# OctoSlime_Switch_Unit.net
KiCad netlist of a schematic drawn in EasyEDA Pro
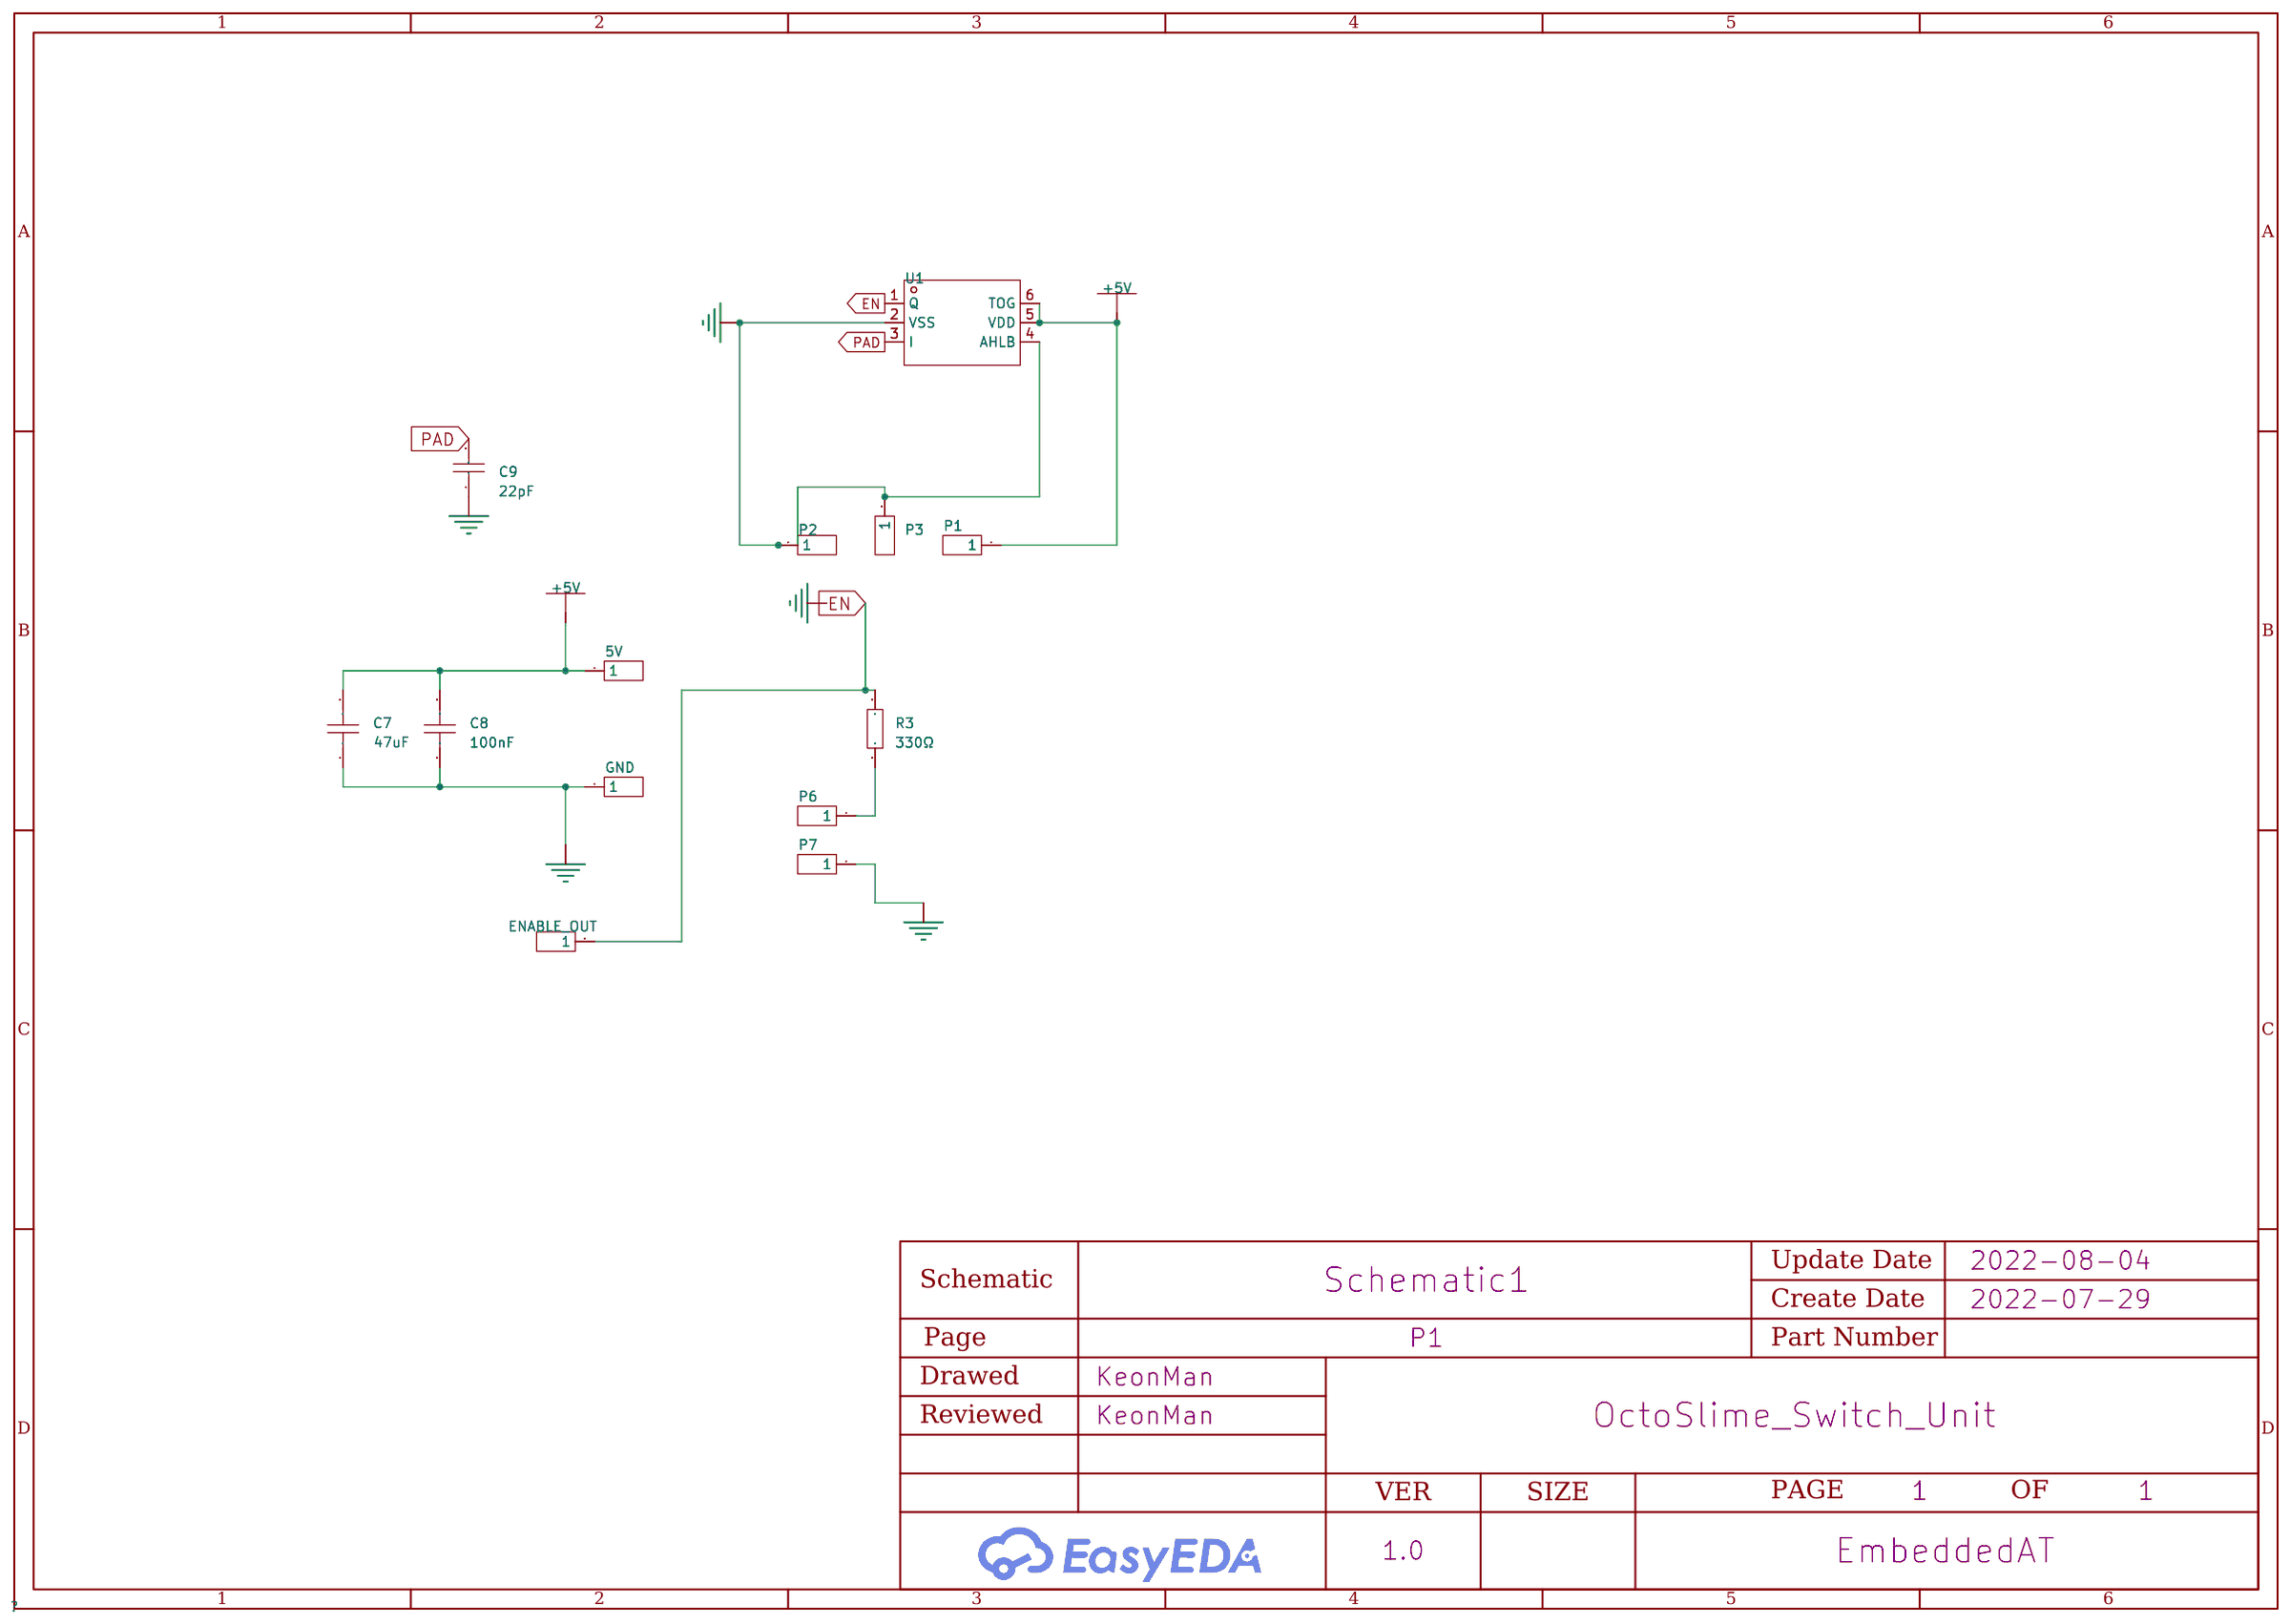
[diagram p0: schematic sheet]

(export (version "E")
  (design (tool "Eeschema 10.0.6"))
  (components
    (comp (ref "5V")
      (value "~")
      (footprint "easyedapro:HDR-TH_1P-P2.54-V-M")
      (description "间距:-;总PIN位数:1;排数:1;插针结构:-;行距:-;安装类型:直插;圆针/方针:-;额定电流:-;额定电压:-;配合针长度:-;塑高:-;触头材质:-;触头镀层:-;颜色:黑色;")
      (fields (field (name "Manufacturer Part") "2.54-1*1P针") (field (name "Manufacturer") "BOOMELE(博穆精密)"))
      (libsource (lib "easyedapro") (part "Header-Male-2.54_1x1"))
    )
    (comp (ref "C7")
      (value "47uF")
      (footprint "easyedapro:C1206")
      (description "容值:47uF;精度:±20%;额定电压:10V;温度系数:X5R;")
      (fields
        (field (name "Manufacturer Part") "CL31A476MPHNNNE")
        (field (name "Manufacturer") "SAMSUNG(三星)")
      )
      (libsource (lib "easyedapro") (part "CL31A476MPHNNNE"))
    )
    (comp (ref "C8")
      (value "100nF")
      (footprint "easyedapro:C0402")
      (description "容值:100nF;精度:±10%;额定电压:50V;温度系数:X7R;")
      (fields
        (field (name "Manufacturer Part") "CL05B104KB54PNC")
        (field (name "Manufacturer") "SAMSUNG(三星)")
      )
      (libsource (lib "easyedapro") (part "CL05B104KB54PNC"))
    )
    (comp (ref "C9")
      (value "22pF")
      (footprint "easyedapro:C0805")
      (description "容值:22pF;精度:±5%;额定电压:50V;温度系数:C0G;")
      (fields
        (field (name "Manufacturer Part") "CL21C220JBANNNC")
        (field (name "Manufacturer") "SAMSUNG(三星)")
      )
      (libsource (lib "easyedapro") (part "CL21C220JBANNNC"))
    )
    (comp (ref "ENABLE_OUT")
      (value "~")
      (footprint "easyedapro:HDR-TH_1P-P2.54-V-M")
      (description "间距:-;总PIN位数:1;排数:1;插针结构:-;行距:-;安装类型:直插;圆针/方针:-;额定电流:-;额定电压:-;配合针长度:-;塑高:-;触头材质:-;触头镀层:-;颜色:黑色;")
      (fields (field (name "Manufacturer Part") "2.54-1*1P针") (field (name "Manufacturer") "BOOMELE(博穆精密)"))
      (libsource (lib "easyedapro") (part "Header-Male-2.54_1x1"))
    )
    (comp (ref "GND")
      (value "~")
      (footprint "easyedapro:HDR-TH_1P-P2.54-V-M")
      (description "间距:-;总PIN位数:1;排数:1;插针结构:-;行距:-;安装类型:直插;圆针/方针:-;额定电流:-;额定电压:-;配合针长度:-;塑高:-;触头材质:-;触头镀层:-;颜色:黑色;")
      (fields (field (name "Manufacturer Part") "2.54-1*1P针") (field (name "Manufacturer") "BOOMELE(博穆精密)"))
      (libsource (lib "easyedapro") (part "Header-Male-2.54_1x1"))
    )
    (comp (ref "P1")
      (value "~")
      (footprint "easyedapro:HDR-TH_1P-P2.54-V-M")
      (description "间距:-;总PIN位数:1;排数:1;插针结构:-;行距:-;安装类型:直插;圆针/方针:-;额定电流:-;额定电压:-;配合针长度:-;塑高:-;触头材质:-;触头镀层:-;颜色:黑色;")
      (fields (field (name "Manufacturer Part") "2.54-1*1P针") (field (name "Manufacturer") "BOOMELE(博穆精密)"))
      (libsource (lib "easyedapro") (part "Header-Male-2.54_1x1"))
    )
    (comp (ref "P2")
      (value "~")
      (footprint "easyedapro:HDR-TH_1P-P2.54-V-M")
      (description "间距:-;总PIN位数:1;排数:1;插针结构:-;行距:-;安装类型:直插;圆针/方针:-;额定电流:-;额定电压:-;配合针长度:-;塑高:-;触头材质:-;触头镀层:-;颜色:黑色;")
      (fields (field (name "Manufacturer Part") "2.54-1*1P针") (field (name "Manufacturer") "BOOMELE(博穆精密)"))
      (libsource (lib "easyedapro") (part "Header-Male-2.54_1x1"))
    )
    (comp (ref "P3")
      (value "~")
      (footprint "easyedapro:HDR-TH_1P-P2.54-V-M")
      (description "间距:-;总PIN位数:1;排数:1;插针结构:-;行距:-;安装类型:直插;圆针/方针:-;额定电流:-;额定电压:-;配合针长度:-;塑高:-;触头材质:-;触头镀层:-;颜色:黑色;")
      (fields (field (name "Manufacturer Part") "2.54-1*1P针") (field (name "Manufacturer") "BOOMELE(博穆精密)"))
      (libsource (lib "easyedapro") (part "Header-Male-2.54_1x1"))
    )
    (comp (ref "P6")
      (value "~")
      (footprint "easyedapro:HDR-TH_1P-P2.54-V-M")
      (description "间距:-;总PIN位数:1;排数:1;插针结构:-;行距:-;安装类型:直插;圆针/方针:-;额定电流:-;额定电压:-;配合针长度:-;塑高:-;触头材质:-;触头镀层:-;颜色:黑色;")
      (fields (field (name "Manufacturer Part") "2.54-1*1P针") (field (name "Manufacturer") "BOOMELE(博穆精密)"))
      (libsource (lib "easyedapro") (part "Header-Male-2.54_1x1"))
    )
    (comp (ref "P7")
      (value "~")
      (footprint "easyedapro:HDR-TH_1P-P2.54-V-M")
      (description "间距:-;总PIN位数:1;排数:1;插针结构:-;行距:-;安装类型:直插;圆针/方针:-;额定电流:-;额定电压:-;配合针长度:-;塑高:-;触头材质:-;触头镀层:-;颜色:黑色;")
      (fields (field (name "Manufacturer Part") "2.54-1*1P针") (field (name "Manufacturer") "BOOMELE(博穆精密)"))
      (libsource (lib "easyedapro") (part "Header-Male-2.54_1x1"))
    )
    (comp (ref "R3")
      (value "330Ω")
      (footprint "easyedapro:R0805")
      (description "电阻类型:厚膜电阻;阻值:330Ω;精度:±1%;功率:125mW;温度系数:±100ppm/;最大工作电压:150V;工作温度范围:-55~+155;")
      (fields
        (field (name "Manufacturer Part") "0805W8F3300T5E")
        (field (name "Manufacturer") "UNI-ROYAL(厚声)")
      )
      (libsource (lib "easyedapro") (part "0805W8F3300T5E"))
    )
    (comp (ref "U1")
      (value "~")
      (footprint "easyedapro:SOT-23-6_L2.9-W1.6-P0.95-LS2.8-BR")
      (description "单按键触摸感应开关")
      (fields (field (name "Manufacturer Part") "TTP223E-BA6") (field (name "Manufacturer") "TONTEK(台湾通泰)"))
      (libsource (lib "easyedapro") (part "TTP223E-BA6"))
    )
  )
  (nets
    (net (code "1") (name "+5V") (class "Default")
      (node (ref "5V") (pin "1") (pinfunction "1_1") (pintype "input"))
      (node (ref "C7") (pin "2") (pinfunction "2_2") (pintype "input"))
      (node (ref "C8") (pin "2") (pinfunction "2_2") (pintype "input"))
      (node (ref "P1") (pin "1") (pinfunction "1_1") (pintype "input"))
      (node (ref "U1") (pin "5") (pinfunction "VDD_5") (pintype "input"))
      (node (ref "U1") (pin "6") (pinfunction "TOG_6") (pintype "input"))
    )
    (net (code "2") (name "EN") (class "Default")
      (node (ref "ENABLE_OUT") (pin "1") (pinfunction "1_1") (pintype "input"))
      (node (ref "R3") (pin "2") (pinfunction "2_2") (pintype "input"))
      (node (ref "U1") (pin "1") (pinfunction "Q_1") (pintype "input"))
    )
    (net (code "3") (name "GND") (class "Default")
      (node (ref "C7") (pin "1") (pinfunction "1_1") (pintype "input"))
      (node (ref "C8") (pin "1") (pinfunction "1_1") (pintype "input"))
      (node (ref "C9") (pin "1") (pinfunction "1_1") (pintype "input"))
      (node (ref "GND") (pin "1") (pinfunction "1_1") (pintype "input"))
      (node (ref "P2") (pin "1") (pinfunction "1_1") (pintype "input"))
      (node (ref "P3") (pin "1") (pinfunction "1_1") (pintype "input"))
      (node (ref "P7") (pin "1") (pinfunction "1_1") (pintype "input"))
      (node (ref "U1") (pin "2") (pinfunction "VSS_2") (pintype "input"))
      (node (ref "U1") (pin "4") (pinfunction "AHLB_4") (pintype "input"))
    )
    (net (code "4") (name "Net-(P6-Pad1)") (class "Default")
      (node (ref "P6") (pin "1") (pinfunction "1_1") (pintype "input"))
      (node (ref "R3") (pin "1") (pinfunction "1_1") (pintype "input"))
    )
    (net (code "5") (name "PAD") (class "Default")
      (node (ref "C9") (pin "2") (pinfunction "2_2") (pintype "input"))
      (node (ref "U1") (pin "3") (pinfunction "I_3") (pintype "input"))
    )
  )
)
